# hexbot.net
KiCad netlist of a schematic drawn in Altium Designer
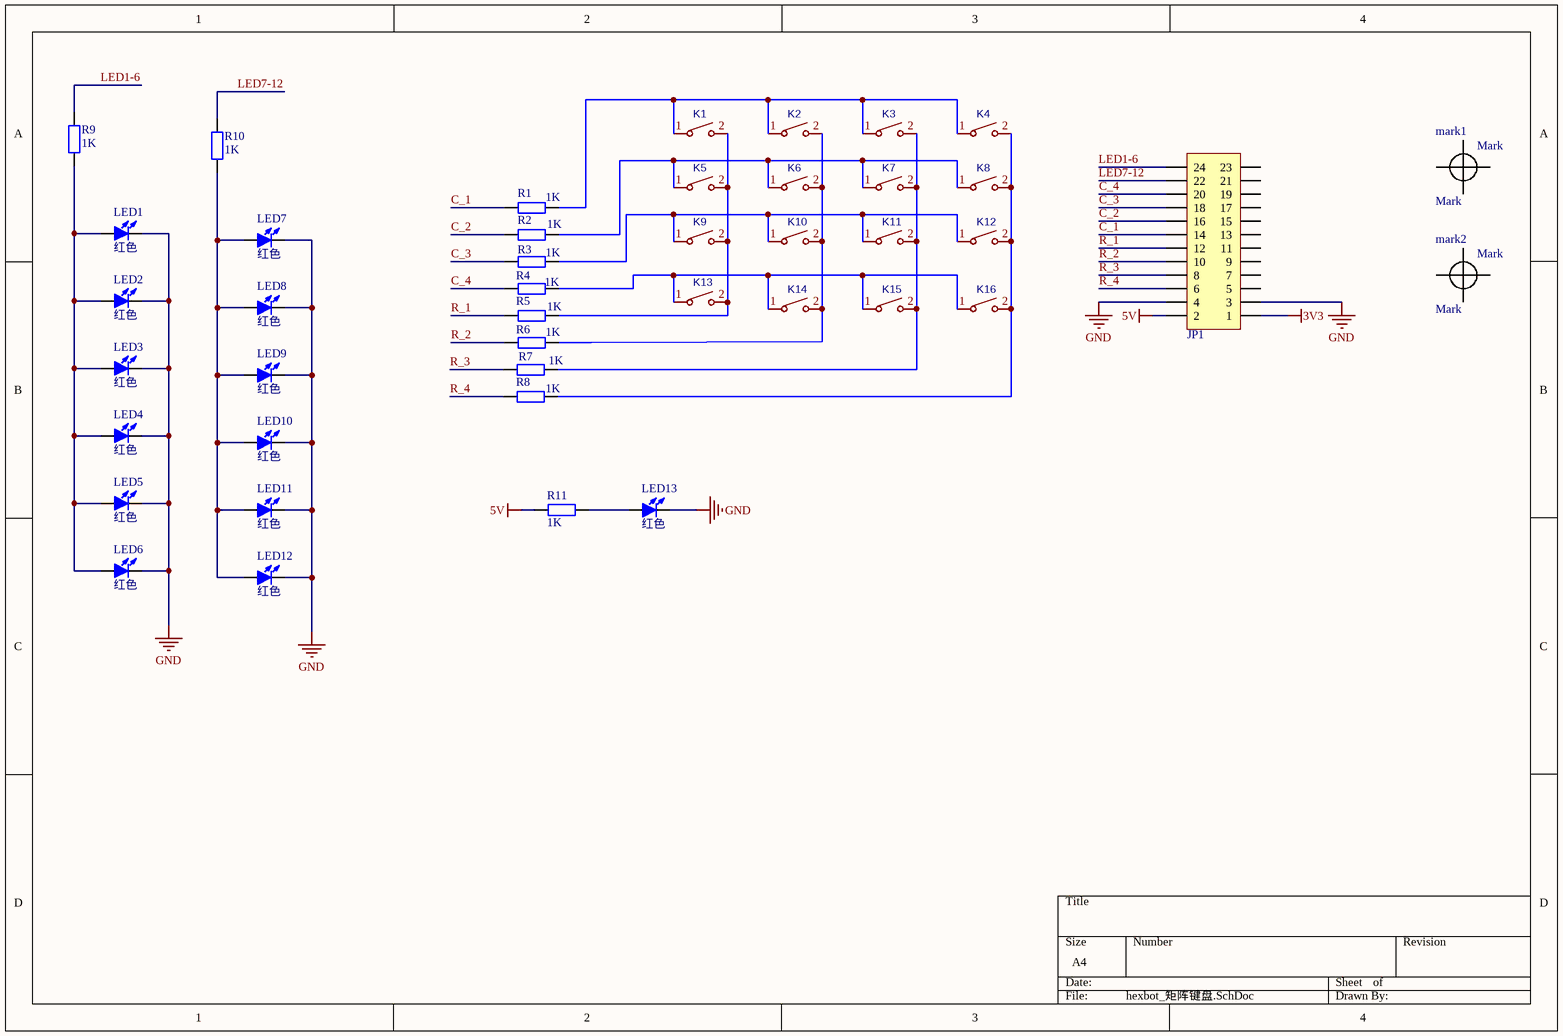
[diagram p0: hexbot_矩阵键盘.SchDoc]

(export (version "E")
  (design (tool "Eeschema 10.0.6"))
  (components
    (comp (ref "JP1")
      (value "Header 2X11")
      (footprint "HDR2.54-WI-2x12P")
      (description "12*2P接插件")
      (fields (field (name "版权归属") "封装库来自淘宝卖家 ID：黄晶宝石"))
      (libsource (lib "5.4 - 接插件-脚距2.54 (100mil) ") (part "Header 12X2"))
    )
    (comp (ref "K1")
      (value "轻触开关3*6*2.5")
      (footprint "按键开关:按键开关")
      (fields (field (name "BOM_SUPPLIER PART") "C9900005901") (field (name "CONTRIBUTOR") "LCSC"))
      (libsource (lib "altium-import") (part "root_0_轻触开关3*6*2.5_"))
    )
    (comp (ref "K2")
      (value "轻触开关3*6*2.5")
      (footprint "按键开关:按键开关")
      (fields (field (name "BOM_SUPPLIER PART") "C9900005901") (field (name "CONTRIBUTOR") "LCSC"))
      (libsource (lib "altium-import") (part "root_0_轻触开关3*6*2.5_"))
    )
    (comp (ref "K3")
      (value "轻触开关3*6*2.5")
      (footprint "按键开关:按键开关")
      (fields (field (name "BOM_SUPPLIER PART") "C9900005901") (field (name "CONTRIBUTOR") "LCSC"))
      (libsource (lib "altium-import") (part "root_0_轻触开关3*6*2.5_"))
    )
    (comp (ref "K4")
      (value "轻触开关3*6*2.5")
      (footprint "按键开关")
      (fields (field (name "BOM_SUPPLIER PART") "C9900005901") (field (name "CONTRIBUTOR") "LCSC"))
      (libsource (lib "altium-import") (part "root_0_轻触开关3*6*2.5_"))
    )
    (comp (ref "K5")
      (value "轻触开关3*6*2.5")
      (footprint "按键开关:按键开关")
      (fields (field (name "BOM_SUPPLIER PART") "C9900005901") (field (name "CONTRIBUTOR") "LCSC"))
      (libsource (lib "altium-import") (part "root_0_轻触开关3*6*2.5_"))
    )
    (comp (ref "K6")
      (value "轻触开关3*6*2.5")
      (footprint "按键开关:按键开关")
      (fields (field (name "BOM_SUPPLIER PART") "C9900005901") (field (name "CONTRIBUTOR") "LCSC"))
      (libsource (lib "altium-import") (part "root_0_轻触开关3*6*2.5_"))
    )
    (comp (ref "K7")
      (value "轻触开关3*6*2.5")
      (footprint "按键开关:按键开关")
      (fields (field (name "BOM_SUPPLIER PART") "C9900005901") (field (name "CONTRIBUTOR") "LCSC"))
      (libsource (lib "altium-import") (part "root_0_轻触开关3*6*2.5_"))
    )
    (comp (ref "K8")
      (value "轻触开关3*6*2.5")
      (footprint "按键开关:按键开关")
      (fields (field (name "BOM_SUPPLIER PART") "C9900005901") (field (name "CONTRIBUTOR") "LCSC"))
      (libsource (lib "altium-import") (part "root_0_轻触开关3*6*2.5_"))
    )
    (comp (ref "K9")
      (value "轻触开关3*6*2.5")
      (footprint "按键开关:按键开关")
      (fields (field (name "BOM_SUPPLIER PART") "C9900005901") (field (name "CONTRIBUTOR") "LCSC"))
      (libsource (lib "altium-import") (part "root_0_轻触开关3*6*2.5_"))
    )
    (comp (ref "K10")
      (value "轻触开关3*6*2.5")
      (footprint "按键开关:按键开关")
      (fields (field (name "BOM_SUPPLIER PART") "C9900005901") (field (name "CONTRIBUTOR") "LCSC"))
      (libsource (lib "altium-import") (part "root_0_轻触开关3*6*2.5_"))
    )
    (comp (ref "K11")
      (value "轻触开关3*6*2.5")
      (footprint "按键开关:按键开关")
      (fields (field (name "BOM_SUPPLIER PART") "C9900005901") (field (name "CONTRIBUTOR") "LCSC"))
      (libsource (lib "altium-import") (part "root_0_轻触开关3*6*2.5_"))
    )
    (comp (ref "K12")
      (value "轻触开关3*6*2.5")
      (footprint "按键开关:按键开关")
      (fields (field (name "BOM_SUPPLIER PART") "C9900005901") (field (name "CONTRIBUTOR") "LCSC"))
      (libsource (lib "altium-import") (part "root_0_轻触开关3*6*2.5_"))
    )
    (comp (ref "K13")
      (value "轻触开关3*6*2.5")
      (footprint "按键开关:按键开关")
      (fields (field (name "BOM_SUPPLIER PART") "C9900005901") (field (name "CONTRIBUTOR") "LCSC"))
      (libsource (lib "altium-import") (part "root_0_轻触开关3*6*2.5_"))
    )
    (comp (ref "K14")
      (value "轻触开关3*6*2.5")
      (footprint "按键开关:按键开关")
      (fields (field (name "BOM_SUPPLIER PART") "C9900005901") (field (name "CONTRIBUTOR") "LCSC"))
      (libsource (lib "altium-import") (part "root_0_轻触开关3*6*2.5_"))
    )
    (comp (ref "K15")
      (value "轻触开关3*6*2.5")
      (footprint "按键开关:按键开关")
      (fields (field (name "BOM_SUPPLIER PART") "C9900005901") (field (name "CONTRIBUTOR") "LCSC"))
      (libsource (lib "altium-import") (part "root_0_轻触开关3*6*2.5_"))
    )
    (comp (ref "K16")
      (value "轻触开关3*6*2.5")
      (footprint "按键开关:按键开关")
      (fields (field (name "BOM_SUPPLIER PART") "C9900005901") (field (name "CONTRIBUTOR") "LCSC"))
      (libsource (lib "altium-import") (part "root_0_轻触开关3*6*2.5_"))
    )
    (comp (ref "LED1")
      (value "红色")
      (footprint "LED 0603R")
      (description "贴片LED")
      (fields (field (name "版权归属") "封装库来自淘宝 ID：黄晶宝石"))
      (libsource (lib "0.3 - LED发光二极管") (part "LED-SMD"))
    )
    (comp (ref "LED2")
      (value "红色")
      (footprint "LED 0603R")
      (description "贴片LED")
      (fields (field (name "版权归属") "封装库来自淘宝 ID：黄晶宝石"))
      (libsource (lib "0.3 - LED发光二极管") (part "LED-SMD"))
    )
    (comp (ref "LED3")
      (value "红色")
      (footprint "LED 0603R")
      (description "贴片LED")
      (fields (field (name "版权归属") "封装库来自淘宝 ID：黄晶宝石"))
      (libsource (lib "0.3 - LED发光二极管") (part "LED-SMD"))
    )
    (comp (ref "LED4")
      (value "红色")
      (footprint "LED 0603R")
      (description "贴片LED")
      (fields (field (name "版权归属") "封装库来自淘宝 ID：黄晶宝石"))
      (libsource (lib "0.3 - LED发光二极管") (part "LED-SMD"))
    )
    (comp (ref "LED5")
      (value "红色")
      (footprint "LED 0603R")
      (description "贴片LED")
      (fields (field (name "版权归属") "封装库来自淘宝 ID：黄晶宝石"))
      (libsource (lib "0.3 - LED发光二极管") (part "LED-SMD"))
    )
    (comp (ref "LED6")
      (value "红色")
      (footprint "LED 0603R")
      (description "贴片LED")
      (fields (field (name "版权归属") "封装库来自淘宝 ID：黄晶宝石"))
      (libsource (lib "0.3 - LED发光二极管") (part "LED-SMD"))
    )
    (comp (ref "LED7")
      (value "红色")
      (footprint "LED 0603R")
      (description "贴片LED")
      (fields (field (name "版权归属") "封装库来自淘宝 ID：黄晶宝石"))
      (libsource (lib "0.3 - LED发光二极管") (part "LED-SMD"))
    )
    (comp (ref "LED8")
      (value "红色")
      (footprint "LED 0603R")
      (description "贴片LED")
      (fields (field (name "版权归属") "封装库来自淘宝 ID：黄晶宝石"))
      (libsource (lib "0.3 - LED发光二极管") (part "LED-SMD"))
    )
    (comp (ref "LED9")
      (value "红色")
      (footprint "LED 0603R")
      (description "贴片LED")
      (fields (field (name "版权归属") "封装库来自淘宝 ID：黄晶宝石"))
      (libsource (lib "0.3 - LED发光二极管") (part "LED-SMD"))
    )
    (comp (ref "LED10")
      (value "红色")
      (footprint "LED 0603R")
      (description "贴片LED")
      (fields (field (name "版权归属") "封装库来自淘宝 ID：黄晶宝石"))
      (libsource (lib "0.3 - LED发光二极管") (part "LED-SMD"))
    )
    (comp (ref "LED11")
      (value "红色")
      (footprint "LED 0603R")
      (description "贴片LED")
      (fields (field (name "版权归属") "封装库来自淘宝 ID：黄晶宝石"))
      (libsource (lib "0.3 - LED发光二极管") (part "LED-SMD"))
    )
    (comp (ref "LED12")
      (value "红色")
      (footprint "LED 0603R")
      (description "贴片LED")
      (fields (field (name "版权归属") "封装库来自淘宝 ID：黄晶宝石"))
      (libsource (lib "0.3 - LED发光二极管") (part "LED-SMD"))
    )
    (comp (ref "LED13")
      (value "红色")
      (footprint "LED 0603R")
      (description "贴片LED")
      (fields (field (name "版权归属") "封装库来自淘宝 ID：黄晶宝石"))
      (libsource (lib "0.3 - LED发光二极管") (part "LED-SMD"))
    )
    (comp (ref "mark1") (value "Mark") (footprint "Mark:Mark") (libsource (lib "Mark") (part "Mark")))
    (comp (ref "mark2") (value "Mark") (footprint "Mark:Mark") (libsource (lib "Mark") (part "Mark")))
    (comp (ref "R1")
      (value "1K")
      (footprint "R 0603_L")
      (description "贴片电阻")
      (fields (field (name "版权归属") "来自淘宝 ID：黄晶宝石"))
      (libsource (lib "0.1 - 电阻-电容-电感") (part "R"))
    )
    (comp (ref "R2")
      (value "1K")
      (footprint "R 0603_L")
      (description "贴片电阻")
      (fields (field (name "版权归属") "来自淘宝 ID：黄晶宝石"))
      (libsource (lib "0.1 - 电阻-电容-电感") (part "R"))
    )
    (comp (ref "R3")
      (value "1K")
      (footprint "R 0603_L")
      (description "贴片电阻")
      (fields (field (name "版权归属") "来自淘宝 ID：黄晶宝石"))
      (libsource (lib "0.1 - 电阻-电容-电感") (part "R"))
    )
    (comp (ref "R4")
      (value "1K")
      (footprint "R 0603_L")
      (description "贴片电阻")
      (fields (field (name "版权归属") "来自淘宝 ID：黄晶宝石"))
      (libsource (lib "0.1 - 电阻-电容-电感") (part "R"))
    )
    (comp (ref "R5")
      (value "1K")
      (footprint "R 0603_L")
      (description "贴片电阻")
      (fields (field (name "版权归属") "来自淘宝 ID：黄晶宝石"))
      (libsource (lib "0.1 - 电阻-电容-电感") (part "R"))
    )
    (comp (ref "R6")
      (value "1K")
      (footprint "R 0603_L")
      (description "贴片电阻")
      (fields (field (name "版权归属") "来自淘宝 ID：黄晶宝石"))
      (libsource (lib "0.1 - 电阻-电容-电感") (part "R"))
    )
    (comp (ref "R7")
      (value "1K")
      (footprint "R 0603_L")
      (description "贴片电阻")
      (fields (field (name "版权归属") "来自淘宝 ID：黄晶宝石"))
      (libsource (lib "0.1 - 电阻-电容-电感") (part "R"))
    )
    (comp (ref "R8")
      (value "1K")
      (footprint "R 0603_L")
      (description "贴片电阻")
      (fields (field (name "版权归属") "来自淘宝 ID：黄晶宝石"))
      (libsource (lib "0.1 - 电阻-电容-电感") (part "R"))
    )
    (comp (ref "R9")
      (value "1K")
      (footprint "R 0603_L")
      (description "贴片电阻")
      (fields (field (name "版权归属") "来自淘宝 ID：黄晶宝石"))
      (libsource (lib "0.1 - 电阻-电容-电感") (part "R"))
    )
    (comp (ref "R10")
      (value "1K")
      (footprint "R 0603_L")
      (description "贴片电阻")
      (fields (field (name "版权归属") "来自淘宝 ID：黄晶宝石"))
      (libsource (lib "0.1 - 电阻-电容-电感") (part "R"))
    )
    (comp (ref "R11")
      (value "1K")
      (footprint "R 0603_L")
      (description "贴片电阻")
      (fields (field (name "版权归属") "来自淘宝 ID：黄晶宝石"))
      (libsource (lib "0.1 - 电阻-电容-电感") (part "R"))
    )
  )
  (nets
    (net (code "1") (name "/C_1") (class "Default")
      (node (ref "JP1") (pin "14") (pinfunction "14_14") (pintype "passive"))
      (node (ref "R1") (pin "1") (pinfunction "1_1") (pintype "passive"))
    )
    (net (code "2") (name "/C_2") (class "Default")
      (node (ref "JP1") (pin "16") (pinfunction "16_16") (pintype "passive"))
      (node (ref "R2") (pin "1") (pinfunction "1_1") (pintype "passive"))
    )
    (net (code "3") (name "/C_3") (class "Default")
      (node (ref "JP1") (pin "18") (pinfunction "18_18") (pintype "passive"))
      (node (ref "R3") (pin "1") (pinfunction "1_1") (pintype "passive"))
    )
    (net (code "4") (name "/C_4") (class "Default")
      (node (ref "JP1") (pin "20") (pinfunction "20_20") (pintype "passive"))
      (node (ref "R4") (pin "1") (pinfunction "1_1") (pintype "passive"))
    )
    (net (code "5") (name "/LED1-6") (class "Default")
      (node (ref "JP1") (pin "24") (pinfunction "24_24") (pintype "passive"))
      (node (ref "R9") (pin "2") (pinfunction "2_2") (pintype "passive"))
    )
    (net (code "6") (name "/LED7-12") (class "Default")
      (node (ref "JP1") (pin "22") (pinfunction "22_22") (pintype "passive"))
      (node (ref "R10") (pin "2") (pinfunction "2_2") (pintype "passive"))
    )
    (net (code "7") (name "/R_1") (class "Default")
      (node (ref "JP1") (pin "12") (pinfunction "12_12") (pintype "passive"))
      (node (ref "R5") (pin "1") (pinfunction "1_1") (pintype "passive"))
    )
    (net (code "8") (name "/R_2") (class "Default")
      (node (ref "JP1") (pin "10") (pinfunction "10_10") (pintype "passive"))
      (node (ref "R6") (pin "1") (pinfunction "1_1") (pintype "passive"))
    )
    (net (code "9") (name "/R_3") (class "Default")
      (node (ref "JP1") (pin "8") (pinfunction "8_8") (pintype "passive"))
      (node (ref "R7") (pin "1") (pinfunction "1_1") (pintype "passive"))
    )
    (net (code "10") (name "/R_4") (class "Default")
      (node (ref "JP1") (pin "6") (pinfunction "6_6") (pintype "passive"))
      (node (ref "R8") (pin "1") (pinfunction "1_1") (pintype "passive"))
    )
    (net (code "11") (name "3V3") (class "Default")
      (node (ref "JP1") (pin "1") (pinfunction "1_1") (pintype "passive"))
    )
    (net (code "12") (name "5V") (class "Default")
      (node (ref "JP1") (pin "2") (pinfunction "2_2") (pintype "passive"))
      (node (ref "R11") (pin "2") (pinfunction "2_2") (pintype "passive"))
    )
    (net (code "13") (name "GND") (class "Default")
      (node (ref "JP1") (pin "3") (pinfunction "3_3") (pintype "passive"))
      (node (ref "JP1") (pin "4") (pinfunction "4_4") (pintype "passive"))
      (node (ref "LED1") (pin "2") (pinfunction "K_2") (pintype "passive"))
      (node (ref "LED10") (pin "2") (pinfunction "K_2") (pintype "passive"))
      (node (ref "LED11") (pin "2") (pinfunction "K_2") (pintype "passive"))
      (node (ref "LED12") (pin "2") (pinfunction "K_2") (pintype "passive"))
      (node (ref "LED13") (pin "2") (pinfunction "K_2") (pintype "passive"))
      (node (ref "LED2") (pin "2") (pinfunction "K_2") (pintype "passive"))
      (node (ref "LED3") (pin "2") (pinfunction "K_2") (pintype "passive"))
      (node (ref "LED4") (pin "2") (pinfunction "K_2") (pintype "passive"))
      (node (ref "LED5") (pin "2") (pinfunction "K_2") (pintype "passive"))
      (node (ref "LED6") (pin "2") (pinfunction "K_2") (pintype "passive"))
      (node (ref "LED7") (pin "2") (pinfunction "K_2") (pintype "passive"))
      (node (ref "LED8") (pin "2") (pinfunction "K_2") (pintype "passive"))
      (node (ref "LED9") (pin "2") (pinfunction "K_2") (pintype "passive"))
    )
    (net (code "14") (name "Net-(K1-Pad1)") (class "Default")
      (node (ref "K1") (pin "1") (pinfunction "1_1") (pintype "passive"))
      (node (ref "K2") (pin "1") (pinfunction "1_1") (pintype "passive"))
      (node (ref "K3") (pin "1") (pinfunction "1_1") (pintype "passive"))
      (node (ref "K4") (pin "1") (pinfunction "1_1") (pintype "passive"))
      (node (ref "R1") (pin "2") (pinfunction "2_2") (pintype "passive"))
    )
    (net (code "15") (name "Net-(K1-Pad2)") (class "Default")
      (node (ref "K1") (pin "2") (pinfunction "2_2") (pintype "passive"))
      (node (ref "K13") (pin "2") (pinfunction "2_2") (pintype "passive"))
      (node (ref "K5") (pin "2") (pinfunction "2_2") (pintype "passive"))
      (node (ref "K9") (pin "2") (pinfunction "2_2") (pintype "passive"))
      (node (ref "R5") (pin "2") (pinfunction "2_2") (pintype "passive"))
    )
    (net (code "16") (name "Net-(K5-Pad1)") (class "Default")
      (node (ref "K5") (pin "1") (pinfunction "1_1") (pintype "passive"))
      (node (ref "K6") (pin "1") (pinfunction "1_1") (pintype "passive"))
      (node (ref "K7") (pin "1") (pinfunction "1_1") (pintype "passive"))
      (node (ref "K8") (pin "1") (pinfunction "1_1") (pintype "passive"))
      (node (ref "R2") (pin "2") (pinfunction "2_2") (pintype "passive"))
    )
    (net (code "17") (name "Net-(K10-Pad1)") (class "Default")
      (node (ref "K10") (pin "1") (pinfunction "1_1") (pintype "passive"))
      (node (ref "K11") (pin "1") (pinfunction "1_1") (pintype "passive"))
      (node (ref "K12") (pin "1") (pinfunction "1_1") (pintype "passive"))
      (node (ref "K9") (pin "1") (pinfunction "1_1") (pintype "passive"))
      (node (ref "R3") (pin "2") (pinfunction "2_2") (pintype "passive"))
    )
    (net (code "18") (name "Net-(K10-Pad2)") (class "Default")
      (node (ref "K10") (pin "2") (pinfunction "2_2") (pintype "passive"))
      (node (ref "K14") (pin "2") (pinfunction "2_2") (pintype "passive"))
      (node (ref "K2") (pin "2") (pinfunction "2_2") (pintype "passive"))
      (node (ref "K6") (pin "2") (pinfunction "2_2") (pintype "passive"))
      (node (ref "R6") (pin "2") (pinfunction "2_2") (pintype "passive"))
    )
    (net (code "19") (name "Net-(K11-Pad2)") (class "Default")
      (node (ref "K11") (pin "2") (pinfunction "2_2") (pintype "passive"))
      (node (ref "K15") (pin "2") (pinfunction "2_2") (pintype "passive"))
      (node (ref "K3") (pin "2") (pinfunction "2_2") (pintype "passive"))
      (node (ref "K7") (pin "2") (pinfunction "2_2") (pintype "passive"))
      (node (ref "R7") (pin "2") (pinfunction "2_2") (pintype "passive"))
    )
    (net (code "20") (name "Net-(K12-Pad2)") (class "Default")
      (node (ref "K12") (pin "2") (pinfunction "2_2") (pintype "passive"))
      (node (ref "K16") (pin "2") (pinfunction "2_2") (pintype "passive"))
      (node (ref "K4") (pin "2") (pinfunction "2_2") (pintype "passive"))
      (node (ref "K8") (pin "2") (pinfunction "2_2") (pintype "passive"))
      (node (ref "R8") (pin "2") (pinfunction "2_2") (pintype "passive"))
    )
    (net (code "21") (name "Net-(K13-Pad1)") (class "Default")
      (node (ref "K13") (pin "1") (pinfunction "1_1") (pintype "passive"))
      (node (ref "K14") (pin "1") (pinfunction "1_1") (pintype "passive"))
      (node (ref "K15") (pin "1") (pinfunction "1_1") (pintype "passive"))
      (node (ref "K16") (pin "1") (pinfunction "1_1") (pintype "passive"))
      (node (ref "R4") (pin "2") (pinfunction "2_2") (pintype "passive"))
    )
    (net (code "22") (name "Net-(LED1-A)") (class "Default")
      (node (ref "LED1") (pin "1") (pinfunction "A_1") (pintype "passive"))
      (node (ref "LED2") (pin "1") (pinfunction "A_1") (pintype "passive"))
      (node (ref "LED3") (pin "1") (pinfunction "A_1") (pintype "passive"))
      (node (ref "LED4") (pin "1") (pinfunction "A_1") (pintype "passive"))
      (node (ref "LED5") (pin "1") (pinfunction "A_1") (pintype "passive"))
      (node (ref "LED6") (pin "1") (pinfunction "A_1") (pintype "passive"))
      (node (ref "R9") (pin "1") (pinfunction "1_1") (pintype "passive"))
    )
    (net (code "23") (name "Net-(LED10-A)") (class "Default")
      (node (ref "LED10") (pin "1") (pinfunction "A_1") (pintype "passive"))
      (node (ref "LED11") (pin "1") (pinfunction "A_1") (pintype "passive"))
      (node (ref "LED12") (pin "1") (pinfunction "A_1") (pintype "passive"))
      (node (ref "LED7") (pin "1") (pinfunction "A_1") (pintype "passive"))
      (node (ref "LED8") (pin "1") (pinfunction "A_1") (pintype "passive"))
      (node (ref "LED9") (pin "1") (pinfunction "A_1") (pintype "passive"))
      (node (ref "R10") (pin "1") (pinfunction "1_1") (pintype "passive"))
    )
    (net (code "24") (name "Net-(LED13-A)") (class "Default")
      (node (ref "LED13") (pin "1") (pinfunction "A_1") (pintype "passive"))
      (node (ref "R11") (pin "1") (pinfunction "1_1") (pintype "passive"))
    )
    (net (code "25") (name "unconnected-(JP1-Pad5)") (class "Default")
      (node (ref "JP1") (pin "5") (pinfunction "5_5") (pintype "passive"))
    )
    (net (code "26") (name "unconnected-(JP1-Pad7)") (class "Default")
      (node (ref "JP1") (pin "7") (pinfunction "7_7") (pintype "passive"))
    )
    (net (code "27") (name "unconnected-(JP1-Pad9)") (class "Default")
      (node (ref "JP1") (pin "9") (pinfunction "9_9") (pintype "passive"))
    )
    (net (code "28") (name "unconnected-(JP1-Pad11)") (class "Default")
      (node (ref "JP1") (pin "11") (pinfunction "11_11") (pintype "passive"))
    )
    (net (code "29") (name "unconnected-(JP1-Pad13)") (class "Default")
      (node (ref "JP1") (pin "13") (pinfunction "13_13") (pintype "passive"))
    )
    (net (code "30") (name "unconnected-(JP1-Pad15)") (class "Default")
      (node (ref "JP1") (pin "15") (pinfunction "15_15") (pintype "passive"))
    )
    (net (code "31") (name "unconnected-(JP1-Pad17)") (class "Default")
      (node (ref "JP1") (pin "17") (pinfunction "17_17") (pintype "passive"))
    )
    (net (code "32") (name "unconnected-(JP1-Pad19)") (class "Default")
      (node (ref "JP1") (pin "19") (pinfunction "19_19") (pintype "passive"))
    )
    (net (code "33") (name "unconnected-(JP1-Pad21)") (class "Default")
      (node (ref "JP1") (pin "21") (pinfunction "21_21") (pintype "passive"))
    )
    (net (code "34") (name "unconnected-(JP1-Pad23)") (class "Default")
      (node (ref "JP1") (pin "23") (pinfunction "23_23") (pintype "passive"))
    )
  )
)
